# BreakoutBoard.net
KiCad netlist of a schematic drawn in EAGLE
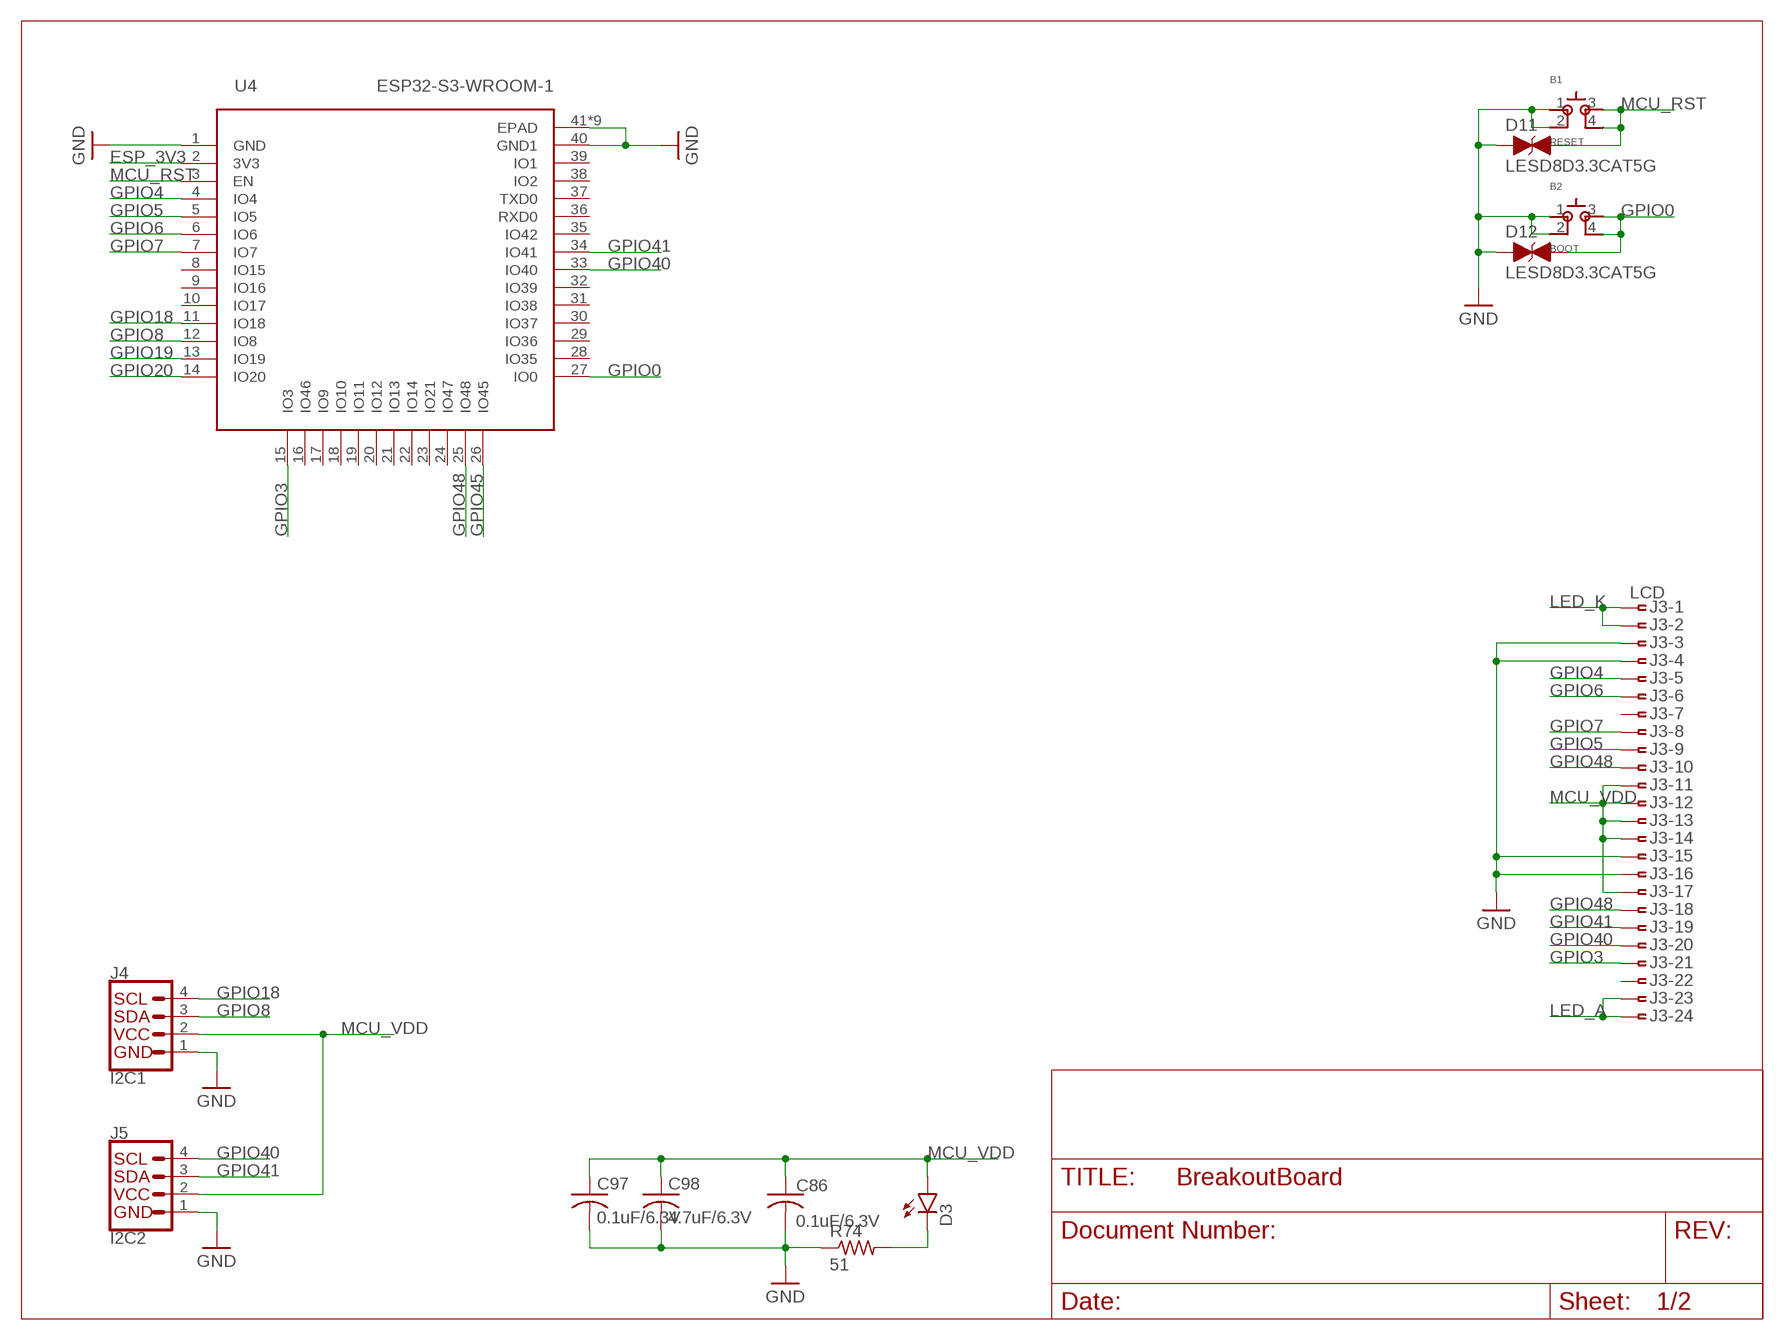
[diagram p0: schematic, sheet 1]
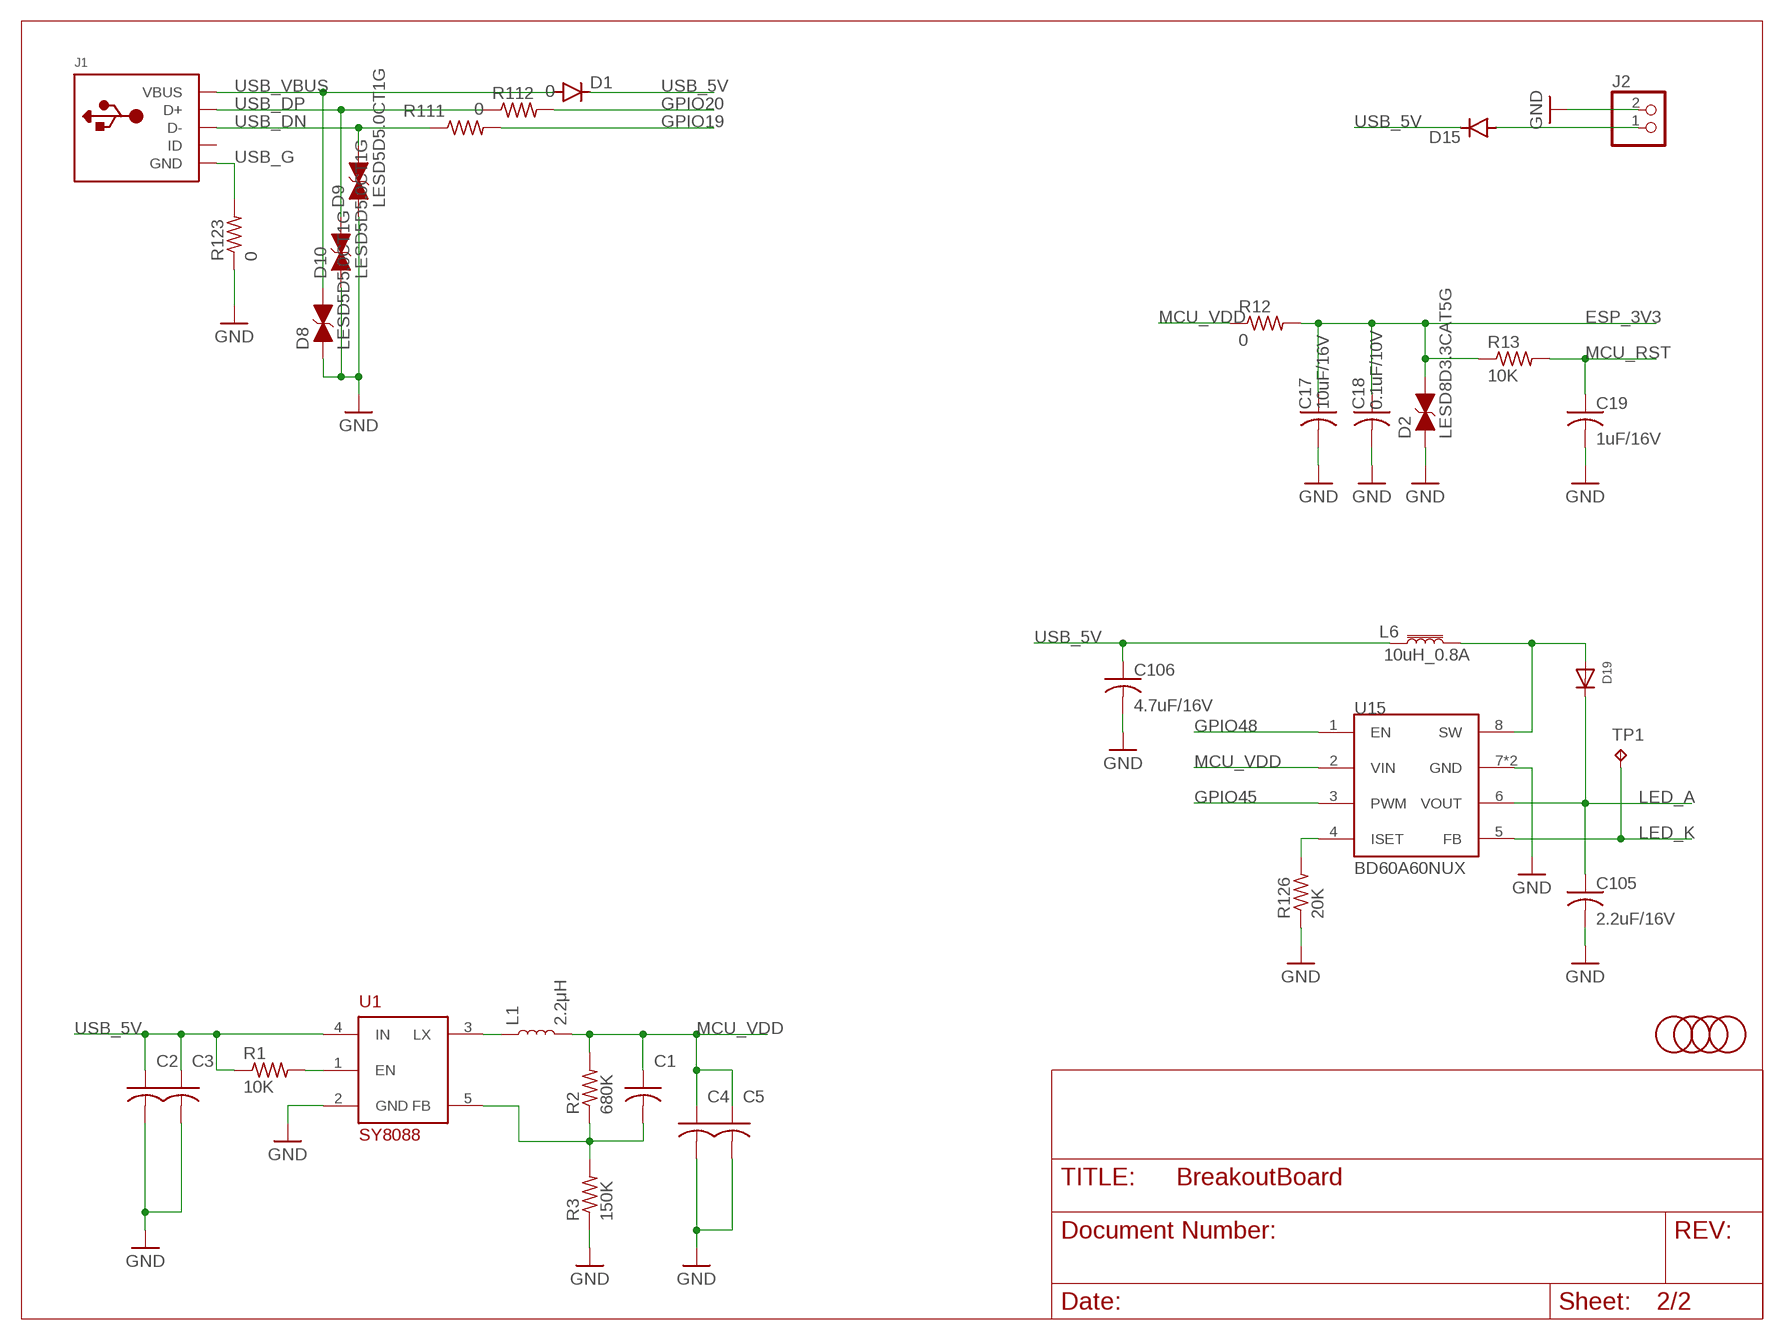
[diagram p1: schematic, sheet 2]

(export (version "E")
  (design (tool "Eeschema 10.0.6"))
  (components
    (comp (ref "B1")
      (value "RESET")
      (footprint "eagle-import:SKSCLDE010")
      (libsource (lib "eagle-import") (part "SKSCLDE010"))
    )
    (comp (ref "B2")
      (value "BOOT")
      (footprint "eagle-import:SKSCLDE010")
      (libsource (lib "eagle-import") (part "SKSCLDE010"))
    )
    (comp (ref "C86")
      (value "0.1uF/6.3V")
      (footprint "eagle-import:C0402")
      (libsource (lib "eagle-import") (part "C-USC0402"))
    )
    (comp (ref "C97")
      (value "0.1uF/6.3V")
      (footprint "eagle-import:C0402")
      (libsource (lib "eagle-import") (part "C-USC0402"))
    )
    (comp (ref "C98")
      (value "4.7uF/6.3V")
      (footprint "eagle-import:C0402")
      (libsource (lib "eagle-import") (part "C-USC0402"))
    )
    (comp (ref "D3")
      (value "LEDCHIPLED_1206")
      (footprint "eagle-import:CHIPLED_1206")
      (libsource (lib "eagle-import") (part "LEDCHIPLED_1206"))
    )
    (comp (ref "D11")
      (value "LESD8D3.3CAT5G")
      (footprint "eagle-import:SOD882")
      (libsource (lib "eagle-import") (part "LESD8D3.3CAT5G"))
    )
    (comp (ref "D12")
      (value "LESD8D3.3CAT5G")
      (footprint "eagle-import:SOD882")
      (libsource (lib "eagle-import") (part "LESD8D3.3CAT5G"))
    )
    (comp (ref "J3")
      (value "LCD")
      (footprint "eagle-import:OK-24F024-04")
      (libsource (lib "eagle-import") (part "ER-CON0.4-24"))
    )
    (comp (ref "J4")
      (value "I2C1")
      (footprint "eagle-import:JST04_1MM_VERT")
      (libsource (lib "eagle-import") (part "QWIIC_CONNECTOR"))
    )
    (comp (ref "J5")
      (value "I2C2")
      (footprint "eagle-import:JST04_1MM_VERT")
      (libsource (lib "eagle-import") (part "QWIIC_CONNECTOR"))
    )
    (comp (ref "R74")
      (value "51")
      (footprint "eagle-import:R0201")
      (libsource (lib "eagle-import") (part "R-US_R0201"))
    )
    (comp (ref "U4")
      (value "ESP32-S3-WROOM-1")
      (footprint "eagle-import:QFN60_ESP32-S3-WROOM-1_EXP")
      (libsource (lib "eagle-import") (part "ESP32-S3-WROOM-1"))
    )
    (comp (ref "C1")
      (value "22pF/50V")
      (footprint "eagle-import:C0402")
      (libsource (lib "eagle-import") (part "C-USC0402"))
    )
    (comp (ref "C2")
      (value "10uF/16V")
      (footprint "eagle-import:C0603")
      (libsource (lib "eagle-import") (part "C-USC0603"))
    )
    (comp (ref "C3")
      (value "0.1uF/10V")
      (footprint "eagle-import:C0603")
      (libsource (lib "eagle-import") (part "C-USC0603"))
    )
    (comp (ref "C4")
      (value "0.1uF/10V")
      (footprint "eagle-import:C0402")
      (libsource (lib "eagle-import") (part "C-USC0402"))
    )
    (comp (ref "C5")
      (value "10uF/16V")
      (footprint "eagle-import:C0402")
      (libsource (lib "eagle-import") (part "C-USC0402"))
    )
    (comp (ref "C17")
      (value "10uF/16V")
      (footprint "eagle-import:C0603")
      (libsource (lib "eagle-import") (part "C-USC0603"))
    )
    (comp (ref "C18")
      (value "0.1uF/10V")
      (footprint "eagle-import:C0402")
      (libsource (lib "eagle-import") (part "C-USC0402"))
    )
    (comp (ref "C19")
      (value "1uF/16V")
      (footprint "eagle-import:C0402")
      (libsource (lib "eagle-import") (part "C-USC0402"))
    )
    (comp (ref "C105")
      (value "2.2uF/16V")
      (footprint "eagle-import:C0603")
      (libsource (lib "eagle-import") (part "C-USC0603"))
    )
    (comp (ref "C106")
      (value "4.7uF/16V")
      (footprint "eagle-import:C0603")
      (libsource (lib "eagle-import") (part "C-USC0603"))
    )
    (comp (ref "D1")
      (value "DIODE-SOD123")
      (footprint "eagle-import:SOD123")
      (libsource (lib "eagle-import") (part "DIODE-SOD123"))
    )
    (comp (ref "D2")
      (value "LESD8D3.3CAT5G")
      (footprint "eagle-import:SOD882")
      (libsource (lib "eagle-import") (part "LESD8D3.3CAT5G"))
    )
    (comp (ref "D8")
      (value "LESD5D5.0CT1G")
      (footprint "eagle-import:SOD523")
      (libsource (lib "eagle-import") (part "LESD5D5.0CT1G"))
    )
    (comp (ref "D9")
      (value "LESD5D5.0CT1G")
      (footprint "eagle-import:SOD523")
      (libsource (lib "eagle-import") (part "LESD5D5.0CT1G"))
    )
    (comp (ref "D10")
      (value "LESD5D5.0CT1G")
      (footprint "eagle-import:SOD523")
      (libsource (lib "eagle-import") (part "LESD5D5.0CT1G"))
    )
    (comp (ref "D15")
      (value "DIODE-SOD123")
      (footprint "eagle-import:SOD123")
      (libsource (lib "eagle-import") (part "DIODE-SOD123"))
    )
    (comp (ref "D19")
      (value "DIODESOD-523")
      (footprint "eagle-import:SOD-523")
      (libsource (lib "eagle-import") (part "DIODESOD-523"))
    )
    (comp (ref "J1")
      (value "MICROBUILDER_USBMICRO_20329")
      (footprint "eagle-import:MICROBUILDER_4UCONN_20329")
      (libsource (lib "eagle-import") (part "MICROBUILDER_USBMICRO_20329"))
    )
    (comp (ref "J2")
      (value "JST_2PIN-SMT")
      (footprint "eagle-import:JST-PH-2-SMT")
      (libsource (lib "eagle-import") (part "JST_2PIN-SMT"))
    )
    (comp (ref "L1")
      (value "2.2μH")
      (footprint "eagle-import:INDUCTOR_4X4MM")
      (libsource (lib "eagle-import") (part "2.2μH-4X4-2.2μH-3A-45MOHM"))
    )
    (comp (ref "L6")
      (value "10uH_0.8A")
      (footprint "eagle-import:L3012S")
      (libsource (lib "eagle-import") (part "SRN3010TA"))
    )
    (comp (ref "R1")
      (value "10K")
      (footprint "eagle-import:R0402")
      (libsource (lib "eagle-import") (part "R-US_R0402"))
    )
    (comp (ref "R2")
      (value "680K")
      (footprint "eagle-import:R0402")
      (libsource (lib "eagle-import") (part "R-US_R0402"))
    )
    (comp (ref "R3")
      (value "150K")
      (footprint "eagle-import:R0402")
      (libsource (lib "eagle-import") (part "R-US_R0402"))
    )
    (comp (ref "R12")
      (value "0")
      (footprint "eagle-import:R0603")
      (libsource (lib "eagle-import") (part "R-US_R0603"))
    )
    (comp (ref "R13")
      (value "10K")
      (footprint "eagle-import:R0402")
      (libsource (lib "eagle-import") (part "R-US_R0402"))
    )
    (comp (ref "R111")
      (value "0")
      (footprint "eagle-import:R0201")
      (libsource (lib "eagle-import") (part "R-US_R0201"))
    )
    (comp (ref "R112")
      (value "0")
      (footprint "eagle-import:R0201")
      (libsource (lib "eagle-import") (part "R-US_R0201"))
    )
    (comp (ref "R123")
      (value "0")
      (footprint "eagle-import:R0603")
      (libsource (lib "eagle-import") (part "R-US_R0603"))
    )
    (comp (ref "R126")
      (value "20K")
      (footprint "eagle-import:R0402")
      (libsource (lib "eagle-import") (part "R-US_R0402"))
    )
    (comp (ref "TP1")
      (value "TPTP06R")
      (footprint "eagle-import:TP06R")
      (libsource (lib "eagle-import") (part "TPTP06R"))
    )
    (comp (ref "U$1")
      (value "FIDUCIAL")
      (footprint "eagle-import:FIDUCIAL_1MM")
      (libsource (lib "eagle-import") (part "FIDUCIAL"))
    )
    (comp (ref "U$2")
      (value "FIDUCIAL")
      (footprint "eagle-import:FIDUCIAL_1MM")
      (libsource (lib "eagle-import") (part "FIDUCIAL"))
    )
    (comp (ref "U$4")
      (value "FIDUCIAL")
      (footprint "eagle-import:FIDUCIAL_1MM")
      (libsource (lib "eagle-import") (part "FIDUCIAL"))
    )
    (comp (ref "U$5")
      (value "FIDUCIAL")
      (footprint "eagle-import:FIDUCIAL_1MM")
      (libsource (lib "eagle-import") (part "FIDUCIAL"))
    )
    (comp (ref "U1")
      (value "SY8088")
      (footprint "eagle-import:SOT23-5")
      (libsource (lib "eagle-import") (part "SY8088"))
    )
    (comp (ref "U15")
      (value "BD60A60NUX")
      (footprint "eagle-import:VSON008X2030")
      (libsource (lib "eagle-import") (part "BD60A60NUX"))
    )
  )
  (nets
    (net (code "1") (name "ESP_3V3") (class "Default")
      (node (ref "C17") (pin "1") (pinfunction "1_1") (pintype "passive"))
      (node (ref "C18") (pin "1") (pinfunction "1_1") (pintype "passive"))
      (node (ref "D2") (pin "C") (pinfunction "C_C") (pintype "passive"))
      (node (ref "R12") (pin "2") (pinfunction "2_2") (pintype "passive"))
      (node (ref "R13") (pin "1") (pinfunction "1_1") (pintype "passive"))
      (node (ref "U4") (pin "2") (pinfunction "3V3_2") (pintype "power_in"))
    )
    (net (code "2") (name "GND") (class "Default")
      (node (ref "B1") (pin "1") (pinfunction "1_1") (pintype "bidirectional"))
      (node (ref "B1") (pin "2") (pinfunction "2_2") (pintype "bidirectional"))
      (node (ref "B2") (pin "1") (pinfunction "1_1") (pintype "bidirectional"))
      (node (ref "B2") (pin "2") (pinfunction "2_2") (pintype "bidirectional"))
      (node (ref "C105") (pin "2") (pinfunction "2_2") (pintype "passive"))
      (node (ref "C106") (pin "2") (pinfunction "2_2") (pintype "passive"))
      (node (ref "C17") (pin "2") (pinfunction "2_2") (pintype "passive"))
      (node (ref "C18") (pin "2") (pinfunction "2_2") (pintype "passive"))
      (node (ref "C19") (pin "2") (pinfunction "2_2") (pintype "passive"))
      (node (ref "C2") (pin "2") (pinfunction "2_2") (pintype "passive"))
      (node (ref "C3") (pin "2") (pinfunction "2_2") (pintype "passive"))
      (node (ref "C4") (pin "2") (pinfunction "2_2") (pintype "passive"))
      (node (ref "C5") (pin "2") (pinfunction "2_2") (pintype "passive"))
      (node (ref "C86") (pin "2") (pinfunction "2_2") (pintype "passive"))
      (node (ref "C97") (pin "2") (pinfunction "2_2") (pintype "passive"))
      (node (ref "C98") (pin "2") (pinfunction "2_2") (pintype "passive"))
      (node (ref "D10") (pin "A") (pinfunction "A_A") (pintype "passive"))
      (node (ref "D11") (pin "A") (pinfunction "A_A") (pintype "passive"))
      (node (ref "D12") (pin "A") (pinfunction "A_A") (pintype "passive"))
      (node (ref "D2") (pin "A") (pinfunction "A_A") (pintype "passive"))
      (node (ref "D8") (pin "A") (pinfunction "A_A") (pintype "passive"))
      (node (ref "D9") (pin "A") (pinfunction "A_A") (pintype "passive"))
      (node (ref "J2") (pin "2") (pinfunction "1_2") (pintype "passive"))
      (node (ref "J3") (pin "15") (pinfunction "1_15") (pintype "passive"))
      (node (ref "J3") (pin "16") (pinfunction "1_16") (pintype "passive"))
      (node (ref "J3") (pin "3") (pinfunction "1_3") (pintype "passive"))
      (node (ref "J3") (pin "4") (pinfunction "1_4") (pintype "passive"))
      (node (ref "J4") (pin "1") (pinfunction "1_1") (pintype "power_in"))
      (node (ref "J5") (pin "1") (pinfunction "1_1") (pintype "power_in"))
      (node (ref "R123") (pin "1") (pinfunction "1_1") (pintype "passive"))
      (node (ref "R126") (pin "1") (pinfunction "1_1") (pintype "passive"))
      (node (ref "R3") (pin "1") (pinfunction "1_1") (pintype "passive"))
      (node (ref "R74") (pin "1") (pinfunction "1_1") (pintype "passive"))
      (node (ref "U1") (pin "2") (pinfunction "GND_2") (pintype "bidirectional"))
      (node (ref "U15") (pin "7") (pinfunction "GND_7") (pintype "bidirectional"))
      (node (ref "U15") (pin "PAD") (pinfunction "GND_PAD") (pintype "bidirectional"))
      (node (ref "U4") (pin "1") (pinfunction "GND_1") (pintype "bidirectional"))
      (node (ref "U4") (pin "40") (pinfunction "GND1_40") (pintype "bidirectional"))
      (node (ref "U4") (pin "41") (pinfunction "EPAD_41") (pintype "bidirectional"))
      (node (ref "U4") (pin "42") (pinfunction "EPAD_42") (pintype "bidirectional"))
      (node (ref "U4") (pin "43") (pinfunction "EPAD_43") (pintype "bidirectional"))
      (node (ref "U4") (pin "44") (pinfunction "EPAD_44") (pintype "bidirectional"))
      (node (ref "U4") (pin "45") (pinfunction "EPAD_45") (pintype "bidirectional"))
      (node (ref "U4") (pin "46") (pinfunction "EPAD_46") (pintype "bidirectional"))
      (node (ref "U4") (pin "47") (pinfunction "EPAD_47") (pintype "bidirectional"))
      (node (ref "U4") (pin "48") (pinfunction "EPAD_48") (pintype "bidirectional"))
      (node (ref "U4") (pin "49") (pinfunction "EPAD_49") (pintype "bidirectional"))
    )
    (net (code "3") (name "GPIO0") (class "Default")
      (node (ref "B2") (pin "3") (pinfunction "4_3") (pintype "bidirectional"))
      (node (ref "B2") (pin "4") (pinfunction "3_4") (pintype "bidirectional"))
      (node (ref "D12") (pin "C") (pinfunction "C_C") (pintype "passive"))
      (node (ref "U4") (pin "27") (pinfunction "IO0_27") (pintype "bidirectional"))
    )
    (net (code "4") (name "GPIO3") (class "Default")
      (node (ref "J3") (pin "21") (pinfunction "1_21") (pintype "passive"))
      (node (ref "U4") (pin "15") (pinfunction "IO3_15") (pintype "bidirectional"))
    )
    (net (code "5") (name "GPIO4") (class "Default")
      (node (ref "J3") (pin "5") (pinfunction "1_5") (pintype "passive"))
      (node (ref "U4") (pin "4") (pinfunction "IO4_4") (pintype "bidirectional"))
    )
    (net (code "6") (name "GPIO5") (class "Default")
      (node (ref "J3") (pin "9") (pinfunction "1_9") (pintype "passive"))
      (node (ref "U4") (pin "5") (pinfunction "IO5_5") (pintype "bidirectional"))
    )
    (net (code "7") (name "GPIO6") (class "Default")
      (node (ref "J3") (pin "6") (pinfunction "1_6") (pintype "passive"))
      (node (ref "U4") (pin "6") (pinfunction "IO6_6") (pintype "bidirectional"))
    )
    (net (code "8") (name "GPIO7") (class "Default")
      (node (ref "J3") (pin "8") (pinfunction "1_8") (pintype "passive"))
      (node (ref "U4") (pin "7") (pinfunction "IO7_7") (pintype "bidirectional"))
    )
    (net (code "9") (name "GPIO8") (class "Default")
      (node (ref "J4") (pin "3") (pinfunction "3_3") (pintype "passive"))
      (node (ref "U4") (pin "12") (pinfunction "IO8_12") (pintype "bidirectional"))
    )
    (net (code "10") (name "GPIO18") (class "Default")
      (node (ref "J4") (pin "4") (pinfunction "4_4") (pintype "passive"))
      (node (ref "U4") (pin "11") (pinfunction "IO18_11") (pintype "bidirectional"))
    )
    (net (code "11") (name "GPIO19") (class "Default")
      (node (ref "R111") (pin "2") (pinfunction "2_2") (pintype "passive"))
      (node (ref "U4") (pin "13") (pinfunction "IO19_13") (pintype "bidirectional"))
    )
    (net (code "12") (name "GPIO20") (class "Default")
      (node (ref "R112") (pin "2") (pinfunction "2_2") (pintype "passive"))
      (node (ref "U4") (pin "14") (pinfunction "IO20_14") (pintype "bidirectional"))
    )
    (net (code "13") (name "GPIO40") (class "Default")
      (node (ref "J3") (pin "20") (pinfunction "1_20") (pintype "passive"))
      (node (ref "J5") (pin "4") (pinfunction "4_4") (pintype "passive"))
      (node (ref "U4") (pin "33") (pinfunction "IO40_33") (pintype "bidirectional"))
    )
    (net (code "14") (name "GPIO41") (class "Default")
      (node (ref "J3") (pin "19") (pinfunction "1_19") (pintype "passive"))
      (node (ref "J5") (pin "3") (pinfunction "3_3") (pintype "passive"))
      (node (ref "U4") (pin "34") (pinfunction "IO41_34") (pintype "bidirectional"))
    )
    (net (code "15") (name "GPIO45") (class "Default")
      (node (ref "U15") (pin "3") (pinfunction "PWM_3") (pintype "bidirectional"))
      (node (ref "U4") (pin "26") (pinfunction "IO45_26") (pintype "bidirectional"))
    )
    (net (code "16") (name "GPIO48") (class "Default")
      (node (ref "J3") (pin "10") (pinfunction "1_10") (pintype "passive"))
      (node (ref "J3") (pin "18") (pinfunction "1_18") (pintype "passive"))
      (node (ref "U15") (pin "1") (pinfunction "EN_1") (pintype "bidirectional"))
      (node (ref "U4") (pin "25") (pinfunction "IO48_25") (pintype "bidirectional"))
    )
    (net (code "17") (name "LED_A") (class "Default")
      (node (ref "C105") (pin "1") (pinfunction "1_1") (pintype "passive"))
      (node (ref "D19") (pin "K") (pinfunction "C_K") (pintype "passive"))
      (node (ref "J3") (pin "23") (pinfunction "1_23") (pintype "passive"))
      (node (ref "J3") (pin "24") (pinfunction "1_24") (pintype "passive"))
      (node (ref "U15") (pin "6") (pinfunction "VOUT_6") (pintype "bidirectional"))
    )
    (net (code "18") (name "LED_K") (class "Default")
      (node (ref "J3") (pin "1") (pinfunction "1_1") (pintype "passive"))
      (node (ref "J3") (pin "2") (pinfunction "1_2") (pintype "passive"))
      (node (ref "TP1") (pin "TP") (pinfunction "TP_TP") (pintype "input"))
      (node (ref "U15") (pin "5") (pinfunction "FB_5") (pintype "bidirectional"))
    )
    (net (code "19") (name "MCU_RST") (class "Default")
      (node (ref "B1") (pin "3") (pinfunction "4_3") (pintype "bidirectional"))
      (node (ref "B1") (pin "4") (pinfunction "3_4") (pintype "bidirectional"))
      (node (ref "C19") (pin "1") (pinfunction "1_1") (pintype "passive"))
      (node (ref "D11") (pin "C") (pinfunction "C_C") (pintype "passive"))
      (node (ref "R13") (pin "2") (pinfunction "2_2") (pintype "passive"))
      (node (ref "U4") (pin "3") (pinfunction "EN_3") (pintype "bidirectional"))
    )
    (net (code "20") (name "MCU_VDD") (class "Default")
      (node (ref "C1") (pin "1") (pinfunction "1_1") (pintype "passive"))
      (node (ref "C4") (pin "1") (pinfunction "1_1") (pintype "passive"))
      (node (ref "C5") (pin "1") (pinfunction "1_1") (pintype "passive"))
      (node (ref "C86") (pin "1") (pinfunction "1_1") (pintype "passive"))
      (node (ref "C97") (pin "1") (pinfunction "1_1") (pintype "passive"))
      (node (ref "C98") (pin "1") (pinfunction "1_1") (pintype "passive"))
      (node (ref "D3") (pin "A") (pinfunction "A_A") (pintype "passive"))
      (node (ref "J3") (pin "11") (pinfunction "1_11") (pintype "passive"))
      (node (ref "J3") (pin "12") (pinfunction "1_12") (pintype "passive"))
      (node (ref "J3") (pin "13") (pinfunction "1_13") (pintype "passive"))
      (node (ref "J3") (pin "14") (pinfunction "1_14") (pintype "passive"))
      (node (ref "J3") (pin "17") (pinfunction "1_17") (pintype "passive"))
      (node (ref "J4") (pin "2") (pinfunction "2_2") (pintype "power_in"))
      (node (ref "J5") (pin "2") (pinfunction "2_2") (pintype "power_in"))
      (node (ref "L1") (pin "P$2") (pinfunction "2_P$2") (pintype "passive"))
      (node (ref "R12") (pin "1") (pinfunction "1_1") (pintype "passive"))
      (node (ref "R2") (pin "2") (pinfunction "2_2") (pintype "passive"))
      (node (ref "U15") (pin "2") (pinfunction "VIN_2") (pintype "bidirectional"))
    )
    (net (code "21") (name "Net-(D3-PadC)") (class "Default")
      (node (ref "D3") (pin "C") (pinfunction "C_C") (pintype "passive"))
      (node (ref "R74") (pin "2") (pinfunction "2_2") (pintype "passive"))
    )
    (net (code "22") (name "Net-(J2-2)") (class "Default")
      (node (ref "D15") (pin "A") (pinfunction "A_A") (pintype "passive"))
      (node (ref "J2") (pin "1") (pinfunction "2_1") (pintype "passive"))
    )
    (net (code "23") (name "Net-(L1-1)") (class "Default")
      (node (ref "L1") (pin "P$1") (pinfunction "1_P$1") (pintype "passive"))
      (node (ref "U1") (pin "3") (pinfunction "LX_3") (pintype "bidirectional"))
    )
    (net (code "24") (name "Net-(L6-2)") (class "Default")
      (node (ref "D19") (pin "A") (pinfunction "A_A") (pintype "passive"))
      (node (ref "L6") (pin "P$2") (pinfunction "2_P$2") (pintype "passive"))
      (node (ref "U15") (pin "8") (pinfunction "SW_8") (pintype "bidirectional"))
    )
    (net (code "25") (name "Net-(U1-EN)") (class "Default")
      (node (ref "R1") (pin "2") (pinfunction "2_2") (pintype "passive"))
      (node (ref "U1") (pin "1") (pinfunction "EN_1") (pintype "bidirectional"))
    )
    (net (code "26") (name "Net-(U1-FB)") (class "Default")
      (node (ref "C1") (pin "2") (pinfunction "2_2") (pintype "passive"))
      (node (ref "R2") (pin "1") (pinfunction "1_1") (pintype "passive"))
      (node (ref "R3") (pin "2") (pinfunction "2_2") (pintype "passive"))
      (node (ref "U1") (pin "5") (pinfunction "FB_5") (pintype "bidirectional"))
    )
    (net (code "27") (name "Net-(U15-ISET)") (class "Default")
      (node (ref "R126") (pin "2") (pinfunction "2_2") (pintype "passive"))
      (node (ref "U15") (pin "4") (pinfunction "ISET_4") (pintype "bidirectional"))
    )
    (net (code "28") (name "USB_5V") (class "Default")
      (node (ref "C106") (pin "1") (pinfunction "1_1") (pintype "passive"))
      (node (ref "C2") (pin "1") (pinfunction "1_1") (pintype "passive"))
      (node (ref "C3") (pin "1") (pinfunction "1_1") (pintype "passive"))
      (node (ref "D1") (pin "C") (pinfunction "C_C") (pintype "passive"))
      (node (ref "D15") (pin "C") (pinfunction "C_C") (pintype "passive"))
      (node (ref "L6") (pin "P$1") (pinfunction "1_P$1") (pintype "passive"))
      (node (ref "R1") (pin "1") (pinfunction "1_1") (pintype "passive"))
      (node (ref "U1") (pin "4") (pinfunction "IN_4") (pintype "bidirectional"))
    )
    (net (code "29") (name "USB_DN") (class "Default")
      (node (ref "D9") (pin "C") (pinfunction "C_C") (pintype "passive"))
      (node (ref "J1") (pin "D-") (pinfunction "D-_D-") (pintype "bidirectional"))
      (node (ref "R111") (pin "1") (pinfunction "1_1") (pintype "passive"))
    )
    (net (code "30") (name "USB_DP") (class "Default")
      (node (ref "D10") (pin "C") (pinfunction "C_C") (pintype "passive"))
      (node (ref "J1") (pin "D+") (pinfunction "D+_D+") (pintype "bidirectional"))
      (node (ref "R112") (pin "1") (pinfunction "1_1") (pintype "passive"))
    )
    (net (code "31") (name "USB_G") (class "Default")
      (node (ref "J1") (pin "BASE@1") (pinfunction "GND_BASE@1") (pintype "power_in"))
      (node (ref "J1") (pin "BASE@2") (pinfunction "GND_BASE@2") (pintype "power_in"))
      (node (ref "J1") (pin "GND") (pinfunction "GND_GND") (pintype "power_in"))
      (node (ref "J1") (pin "SPRT@1") (pinfunction "GND_SPRT@1") (pintype "power_in"))
      (node (ref "J1") (pin "SPRT@2") (pinfunction "GND_SPRT@2") (pintype "power_in"))
      (node (ref "J1") (pin "SPRT@3") (pinfunction "GND_SPRT@3") (pintype "power_in"))
      (node (ref "J1") (pin "SPRT@4") (pinfunction "GND_SPRT@4") (pintype "power_in"))
      (node (ref "R123") (pin "2") (pinfunction "2_2") (pintype "passive"))
    )
    (net (code "32") (name "USB_VBUS") (class "Default")
      (node (ref "D1") (pin "A") (pinfunction "A_A") (pintype "passive"))
      (node (ref "D8") (pin "C") (pinfunction "C_C") (pintype "passive"))
      (node (ref "J1") (pin "VBUS") (pinfunction "VBUS_VBUS") (pintype "power_in"))
    )
    (net (code "33") (name "unconnected-(J1-PadID)") (class "Default")
      (node (ref "J1") (pin "ID") (pinfunction "ID_ID") (pintype "bidirectional"))
    )
    (net (code "34") (name "unconnected-(J3O-1-Pad22)") (class "Default")
      (node (ref "J3") (pin "22") (pinfunction "1_22") (pintype "passive"))
    )
    (net (code "35") (name "unconnected-(J3V-1-Pad7)") (class "Default")
      (node (ref "J3") (pin "7") (pinfunction "1_7") (pintype "passive"))
    )
    (net (code "36") (name "unconnected-(U4-IO1-Pad39)") (class "Default")
      (node (ref "U4") (pin "39") (pinfunction "IO1_39") (pintype "bidirectional"))
    )
    (net (code "37") (name "unconnected-(U4-IO2-Pad38)") (class "Default")
      (node (ref "U4") (pin "38") (pinfunction "IO2_38") (pintype "bidirectional"))
    )
    (net (code "38") (name "unconnected-(U4-IO9-Pad17)") (class "Default")
      (node (ref "U4") (pin "17") (pinfunction "IO9_17") (pintype "bidirectional"))
    )
    (net (code "39") (name "unconnected-(U4-IO10-Pad18)") (class "Default")
      (node (ref "U4") (pin "18") (pinfunction "IO10_18") (pintype "bidirectional"))
    )
    (net (code "40") (name "unconnected-(U4-IO11-Pad19)") (class "Default")
      (node (ref "U4") (pin "19") (pinfunction "IO11_19") (pintype "bidirectional"))
    )
    (net (code "41") (name "unconnected-(U4-IO12-Pad20)") (class "Default")
      (node (ref "U4") (pin "20") (pinfunction "IO12_20") (pintype "bidirectional"))
    )
    (net (code "42") (name "unconnected-(U4-IO13-Pad21)") (class "Default")
      (node (ref "U4") (pin "21") (pinfunction "IO13_21") (pintype "bidirectional"))
    )
    (net (code "43") (name "unconnected-(U4-IO14-Pad22)") (class "Default")
      (node (ref "U4") (pin "22") (pinfunction "IO14_22") (pintype "bidirectional"))
    )
    (net (code "44") (name "unconnected-(U4-IO15-Pad8)") (class "Default")
      (node (ref "U4") (pin "8") (pinfunction "IO15_8") (pintype "bidirectional"))
    )
    (net (code "45") (name "unconnected-(U4-IO16-Pad9)") (class "Default")
      (node (ref "U4") (pin "9") (pinfunction "IO16_9") (pintype "bidirectional"))
    )
    (net (code "46") (name "unconnected-(U4-IO17-Pad10)") (class "Default")
      (node (ref "U4") (pin "10") (pinfunction "IO17_10") (pintype "bidirectional"))
    )
    (net (code "47") (name "unconnected-(U4-IO21-Pad23)") (class "Default")
      (node (ref "U4") (pin "23") (pinfunction "IO21_23") (pintype "bidirectional"))
    )
    (net (code "48") (name "unconnected-(U4-IO35-Pad28)") (class "Default")
      (node (ref "U4") (pin "28") (pinfunction "IO35_28") (pintype "bidirectional"))
    )
    (net (code "49") (name "unconnected-(U4-IO36-Pad29)") (class "Default")
      (node (ref "U4") (pin "29") (pinfunction "IO36_29") (pintype "bidirectional"))
    )
    (net (code "50") (name "unconnected-(U4-IO37-Pad30)") (class "Default")
      (node (ref "U4") (pin "30") (pinfunction "IO37_30") (pintype "bidirectional"))
    )
    (net (code "51") (name "unconnected-(U4-IO38-Pad31)") (class "Default")
      (node (ref "U4") (pin "31") (pinfunction "IO38_31") (pintype "bidirectional"))
    )
    (net (code "52") (name "unconnected-(U4-IO39-Pad32)") (class "Default")
      (node (ref "U4") (pin "32") (pinfunction "IO39_32") (pintype "bidirectional"))
    )
    (net (code "53") (name "unconnected-(U4-IO42-Pad35)") (class "Default")
      (node (ref "U4") (pin "35") (pinfunction "IO42_35") (pintype "bidirectional"))
    )
    (net (code "54") (name "unconnected-(U4-IO46-Pad16)") (class "Default")
      (node (ref "U4") (pin "16") (pinfunction "IO46_16") (pintype "bidirectional"))
    )
    (net (code "55") (name "unconnected-(U4-IO47-Pad24)") (class "Default")
      (node (ref "U4") (pin "24") (pinfunction "IO47_24") (pintype "bidirectional"))
    )
    (net (code "56") (name "unconnected-(U4-RXD0-Pad36)") (class "Default")
      (node (ref "U4") (pin "36") (pinfunction "RXD0_36") (pintype "bidirectional"))
    )
    (net (code "57") (name "unconnected-(U4-TXD0-Pad37)") (class "Default")
      (node (ref "U4") (pin "37") (pinfunction "TXD0_37") (pintype "bidirectional"))
    )
  )
)
